# IR_Sensor.net
KiCad netlist of a schematic drawn in Altium Designer
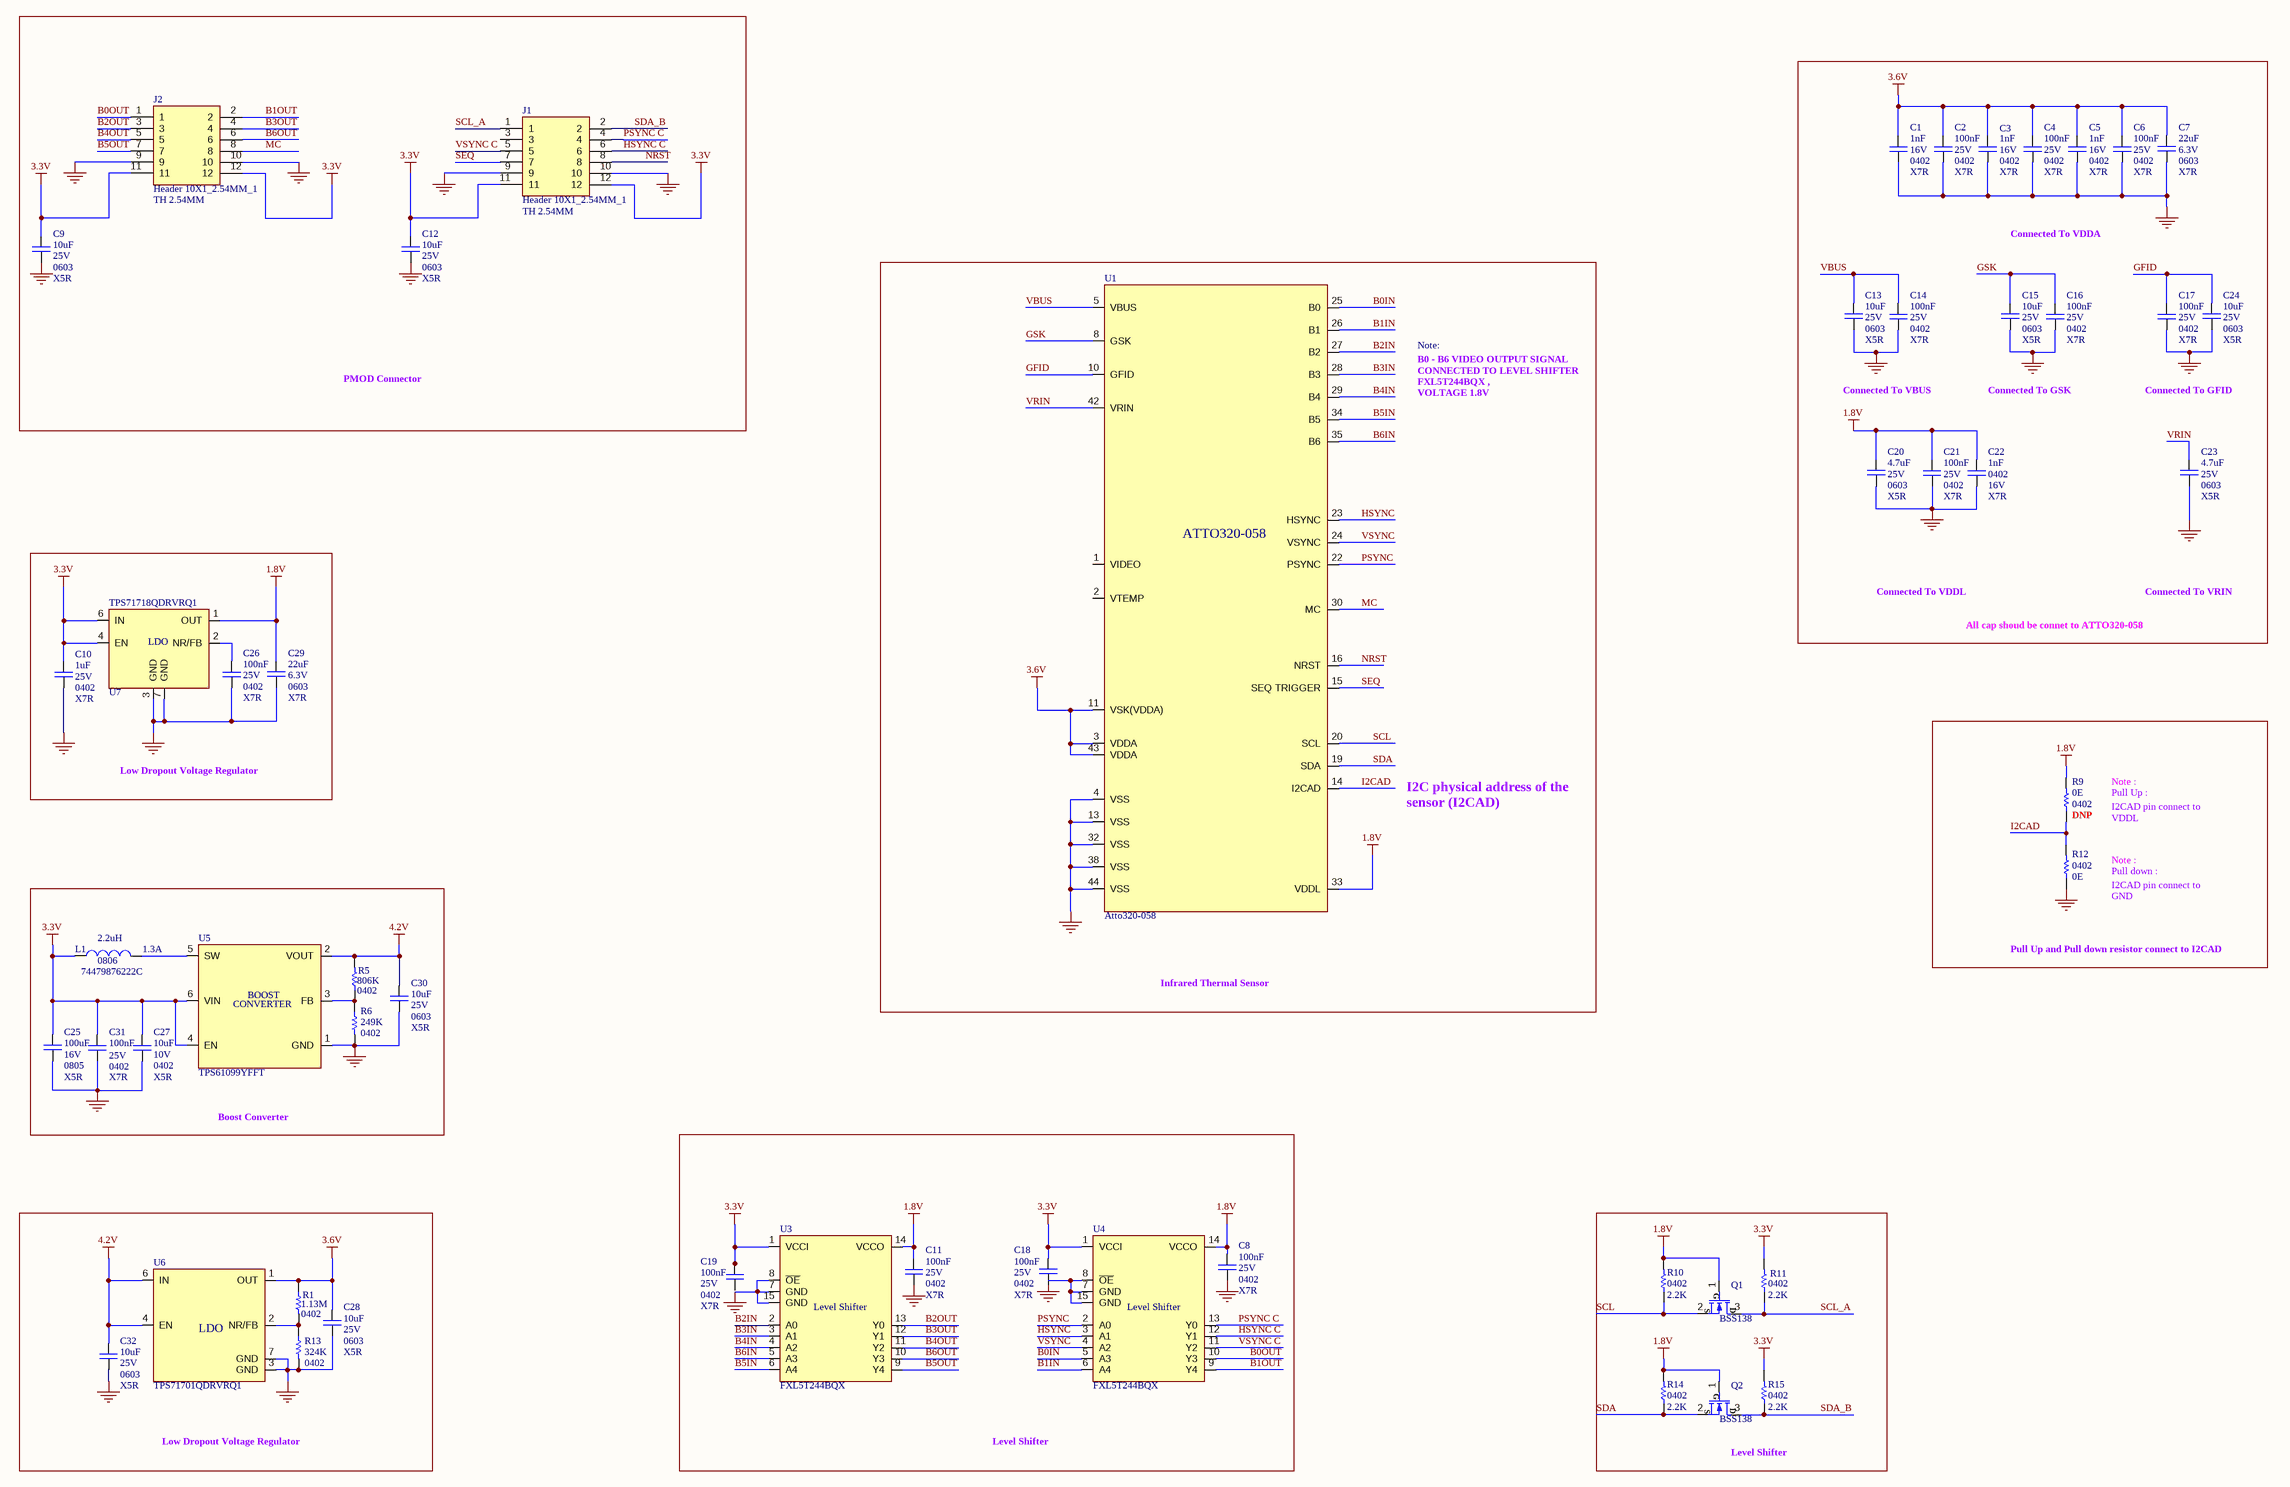
[diagram p0: IR_Sensor.SchDoc]

(export (version "E")
  (design (tool "Eeschema 10.0.6"))
  (components
    (comp (ref "C1")
      (value "1nF")
      (footprint "CAPC0402")
      (description "CAP CER 1nF 16V X7R 0402")
      (fields
        (field (name "VOLTAGE") "16V")
        (field (name "CASE/PACKAGE") "0402")
        (field (name "DIELECTRIC") "X7R")
        (field (name "Comment") "Cap")
      )
      (libsource (lib "CUSTOM TNY290PG") (part "Cap"))
    )
    (comp (ref "C2")
      (value "100nF")
      (footprint "CAPC0402")
      (description "CAP CER 100nF 25V X7R 0402")
      (fields
        (field (name "VOLTAGE") "25V")
        (field (name "CASE/PACKAGE") "0402")
        (field (name "DIELECTRIC") "X7R")
        (field (name "Comment") "Cap")
      )
      (libsource (lib "CUSTOM TNY290PG") (part "Cap"))
    )
    (comp (ref "C3")
      (value "1nF")
      (footprint "CAPC0402")
      (description "CAP CER 1nF 16V X7R 0402")
      (fields
        (field (name "VOLTAGE") "16V")
        (field (name "CASE/PACKAGE") "0402")
        (field (name "DIELECTRIC") "X7R")
        (field (name "Comment") "Cap")
      )
      (libsource (lib "CUSTOM TNY290PG") (part "Cap"))
    )
    (comp (ref "C4")
      (value "100nF")
      (footprint "CAPC0402")
      (description "CAP CER 100nF 25V X7R 0402")
      (fields
        (field (name "VOLTAGE") "25V")
        (field (name "CASE/PACKAGE") "0402")
        (field (name "DIELECTRIC") "X7R")
        (field (name "Comment") "Cap")
      )
      (libsource (lib "CUSTOM TNY290PG") (part "Cap"))
    )
    (comp (ref "C5")
      (value "1nF")
      (footprint "CAPC0402")
      (description "CAP CER 1nF 16V X7R 0402")
      (fields
        (field (name "VOLTAGE") "16V")
        (field (name "CASE/PACKAGE") "0402")
        (field (name "DIELECTRIC") "X7R")
        (field (name "Comment") "Cap")
      )
      (libsource (lib "CUSTOM TNY290PG") (part "Cap"))
    )
    (comp (ref "C6")
      (value "100nF")
      (footprint "CAPC0402")
      (description "CAP CER 100nF 25V X7R 0402")
      (fields
        (field (name "VOLTAGE") "25V")
        (field (name "CASE/PACKAGE") "0402")
        (field (name "DIELECTRIC") "X7R")
        (field (name "Comment") "Cap")
      )
      (libsource (lib "CUSTOM TNY290PG") (part "Cap"))
    )
    (comp (ref "C7")
      (value "22uF")
      (footprint "CAPC0603")
      (description "CAP CER 22uF 6.3V X7R 0603")
      (fields
        (field (name "VOLTAGE") "6.3V")
        (field (name "CASE/PACKAGE") "0603")
        (field (name "DIELECTRIC") "X7R")
        (field (name "Comment") "Cap")
      )
      (libsource (lib "CUSTOM TNY290PG") (part "Cap"))
    )
    (comp (ref "C8")
      (value "100nF")
      (footprint "CAPC0402")
      (description "CAP CER 100nF 25V X7R 0402")
      (fields
        (field (name "VOLTAGE") "25V")
        (field (name "CASE/PACKAGE") "0402")
        (field (name "DIELECTRIC") "X7R")
        (field (name "Comment") "Cap")
      )
      (libsource (lib "CUSTOM TNY290PG") (part "Cap"))
    )
    (comp (ref "C9")
      (value "10uF")
      (footprint "CAPC0603")
      (description "CAP CER 10uF 25V X5R 0603")
      (fields
        (field (name "VOLTAGE") "25V")
        (field (name "CASE/PACKAGE") "0603")
        (field (name "DIELECTRIC") "X5R")
        (field (name "Comment") "Cap")
      )
      (libsource (lib "CUSTOM TNY290PG") (part "Cap"))
    )
    (comp (ref "C10")
      (value "1uF")
      (footprint "CAPC0402")
      (description "CAP CER 1uF 25V X7R 0402")
      (fields
        (field (name "VOLTAGE") "25V")
        (field (name "CASE/PACKAGE") "0402")
        (field (name "DIELECTRIC") "X7R")
        (field (name "Comment") "Cap")
      )
      (libsource (lib "CUSTOM TNY290PG") (part "Cap"))
    )
    (comp (ref "C11")
      (value "100nF")
      (footprint "CAPC0402")
      (description "CAP CER 100nF 25V X7R 0402")
      (fields
        (field (name "VOLTAGE") "25V")
        (field (name "CASE/PACKAGE") "0402")
        (field (name "DIELECTRIC") "X7R")
        (field (name "Comment") "Cap")
      )
      (libsource (lib "CUSTOM TNY290PG") (part "Cap"))
    )
    (comp (ref "C12")
      (value "10uF")
      (footprint "CAPC0603")
      (description "CAP CER 10uF 25V X5R 0603")
      (fields
        (field (name "VOLTAGE") "25V")
        (field (name "CASE/PACKAGE") "0603")
        (field (name "DIELECTRIC") "X5R")
        (field (name "Comment") "Cap")
      )
      (libsource (lib "CUSTOM TNY290PG") (part "Cap"))
    )
    (comp (ref "C13")
      (value "10uF")
      (footprint "CAPC0603")
      (description "CAP CER 10uF 25V X5R 0603")
      (fields
        (field (name "VOLTAGE") "25V")
        (field (name "CASE/PACKAGE") "0603")
        (field (name "DIELECTRIC") "X5R")
        (field (name "Comment") "Cap")
      )
      (libsource (lib "CUSTOM TNY290PG") (part "Cap"))
    )
    (comp (ref "C14")
      (value "100nF")
      (footprint "CAPC0402")
      (description "CAP CER 100nF 25V X7R 0402")
      (fields
        (field (name "VOLTAGE") "25V")
        (field (name "CASE/PACKAGE") "0402")
        (field (name "DIELECTRIC") "X7R")
        (field (name "Comment") "Cap")
      )
      (libsource (lib "CUSTOM TNY290PG") (part "Cap"))
    )
    (comp (ref "C15")
      (value "10uF")
      (footprint "CAPC0603")
      (description "CAP CER 10uF 25V X5R 0603")
      (fields
        (field (name "VOLTAGE") "25V")
        (field (name "CASE/PACKAGE") "0603")
        (field (name "DIELECTRIC") "X5R")
        (field (name "Comment") "Cap")
      )
      (libsource (lib "CUSTOM TNY290PG") (part "Cap"))
    )
    (comp (ref "C16")
      (value "100nF")
      (footprint "CAPC0402")
      (description "CAP CER 100nF 25V X7R 0402")
      (fields
        (field (name "VOLTAGE") "25V")
        (field (name "CASE/PACKAGE") "0402")
        (field (name "DIELECTRIC") "X7R")
        (field (name "Comment") "Cap")
      )
      (libsource (lib "CUSTOM TNY290PG") (part "Cap"))
    )
    (comp (ref "C17")
      (value "100nF")
      (footprint "CAPC0402")
      (description "CAP CER 100nF 25V X7R 0402")
      (fields
        (field (name "VOLTAGE") "25V")
        (field (name "CASE/PACKAGE") "0402")
        (field (name "DIELECTRIC") "X7R")
        (field (name "Comment") "Cap")
      )
      (libsource (lib "CUSTOM TNY290PG") (part "Cap"))
    )
    (comp (ref "C18")
      (value "100nF")
      (footprint "CAPC0402")
      (description "CAP CER 100nF 25V X7R 0402")
      (fields
        (field (name "VOLTAGE") "25V")
        (field (name "CASE/PACKAGE") "0402")
        (field (name "DIELECTRIC") "X7R")
        (field (name "Comment") "Cap")
      )
      (libsource (lib "CUSTOM TNY290PG") (part "Cap"))
    )
    (comp (ref "C19")
      (value "100nF")
      (footprint "CAPC0402")
      (description "CAP CER 100nF 25V X7R 0402")
      (fields
        (field (name "VOLTAGE") "25V")
        (field (name "CASE/PACKAGE") "0402")
        (field (name "DIELECTRIC") "X7R")
        (field (name "Comment") "Cap")
      )
      (libsource (lib "CUSTOM TNY290PG") (part "Cap"))
    )
    (comp (ref "C20")
      (value "4.7uF")
      (footprint "CAPC0603")
      (description "CAP CER 4.7uF 25V X5R 0603")
      (fields
        (field (name "CASE/PACKAGE") "0603")
        (field (name "DIELECTRIC") "X5R")
        (field (name "VOLTAGE") "25V")
        (field (name "Comment") "Cap")
      )
      (libsource (lib "CUSTOM TNY290PG") (part "Cap"))
    )
    (comp (ref "C21")
      (value "100nF")
      (footprint "CAPC0402")
      (description "CAP CER 100nF 25V X7R 0402")
      (fields
        (field (name "VOLTAGE") "25V")
        (field (name "CASE/PACKAGE") "0402")
        (field (name "DIELECTRIC") "X7R")
        (field (name "Comment") "Cap")
      )
      (libsource (lib "CUSTOM TNY290PG") (part "Cap"))
    )
    (comp (ref "C22")
      (value "1nF")
      (footprint "CAPC0402")
      (description "CAP CER 1nF 16V X7R 0402")
      (fields
        (field (name "VOLTAGE") "16V")
        (field (name "CASE/PACKAGE") "0402")
        (field (name "DIELECTRIC") "X7R")
        (field (name "Comment") "Cap")
      )
      (libsource (lib "CUSTOM TNY290PG") (part "Cap"))
    )
    (comp (ref "C23")
      (value "4.7uF")
      (footprint "CAPC0603")
      (description "CAP CER 4.7uF 25V X5R 0603")
      (fields
        (field (name "VOLTAGE") "25V")
        (field (name "CASE/PACKAGE") "0603")
        (field (name "DIELECTRIC") "X5R")
        (field (name "Comment") "Cap")
      )
      (libsource (lib "CUSTOM TNY290PG") (part "Cap"))
    )
    (comp (ref "C24")
      (value "10uF")
      (footprint "CAPC0603")
      (description "CAP CER 10uF 25V X5R 0603")
      (fields
        (field (name "VOLTAGE") "25V")
        (field (name "CASE/PACKAGE") "0603")
        (field (name "DIELECTRIC") "X5R")
        (field (name "Comment") "Cap")
      )
      (libsource (lib "CUSTOM TNY290PG") (part "Cap"))
    )
    (comp (ref "C25")
      (value "100uF")
      (footprint "CAPC0805")
      (description "CAP CER 100uF 16V X5R 0805")
      (fields
        (field (name "CASE/PACKAGE") "0805")
        (field (name "DIELECTRIC") "X5R")
        (field (name "VOLTAGE") "16V")
        (field (name "Comment") "Cap")
      )
      (libsource (lib "CUSTOM TNY290PG") (part "Cap"))
    )
    (comp (ref "C26")
      (value "100nF")
      (footprint "CAPC0402")
      (description "CAP CER 100nF 25V X7R 0402")
      (fields
        (field (name "VOLTAGE") "25V")
        (field (name "CASE/PACKAGE") "0402")
        (field (name "DIELECTRIC") "X7R")
        (field (name "Comment") "Cap")
      )
      (libsource (lib "CUSTOM TNY290PG") (part "Cap"))
    )
    (comp (ref "C27")
      (value "10uF")
      (footprint "CAPC0402")
      (description "CAP CER 10uF 0402 10V X5R")
      (fields
        (field (name "VOLTAGE") "10V")
        (field (name "CASE/PACKAGE") "0402")
        (field (name "DIELECTRIC") "X5R")
        (field (name "Comment") "Cap")
      )
      (libsource (lib "CUSTOM TNY290PG") (part "Cap"))
    )
    (comp (ref "C28")
      (value "10uF")
      (footprint "CAPC0603")
      (description "CAP CER 10uF 25V X5R 0603")
      (fields
        (field (name "VOLTAGE") "25V")
        (field (name "CASE/PACKAGE") "0603")
        (field (name "DIELECTRIC") "X5R")
        (field (name "Comment") "Cap")
      )
      (libsource (lib "CUSTOM TNY290PG") (part "Cap"))
    )
    (comp (ref "C29")
      (value "22uF")
      (footprint "CAPC0603")
      (description "CAP CER 22uF 6.3V X7R 0603")
      (fields
        (field (name "VOLTAGE") "6.3V")
        (field (name "CASE/PACKAGE") "0603")
        (field (name "DIELECTRIC") "X7R")
        (field (name "Comment") "Cap")
      )
      (libsource (lib "CUSTOM TNY290PG") (part "Cap"))
    )
    (comp (ref "C30")
      (value "10uF")
      (footprint "CAPC0603")
      (description "CAP CER 10uF 25V X5R 0603")
      (fields
        (field (name "VOLTAGE") "25V")
        (field (name "CASE/PACKAGE") "0603")
        (field (name "DIELECTRIC") "X5R")
        (field (name "Comment") "Cap")
      )
      (libsource (lib "CUSTOM TNY290PG") (part "Cap"))
    )
    (comp (ref "C31")
      (value "100nF")
      (footprint "CAPC0402")
      (description "CAP CER 100nF 25V X7R 0402")
      (fields
        (field (name "VOLTAGE") "25V")
        (field (name "CASE/PACKAGE") "0402")
        (field (name "DIELECTRIC") "X7R")
        (field (name "Comment") "Cap")
      )
      (libsource (lib "CUSTOM TNY290PG") (part "Cap"))
    )
    (comp (ref "C32")
      (value "10uF")
      (footprint "CAPC0603")
      (description "CAP CER 10uF 25V X5R 0603")
      (fields
        (field (name "VOLTAGE") "25V")
        (field (name "CASE/PACKAGE") "0603")
        (field (name "DIELECTRIC") "X5R")
        (field (name "Comment") "Cap")
      )
      (libsource (lib "CUSTOM TNY290PG") (part "Cap"))
    )
    (comp (ref "J1")
      (value "Header 10X1_2.54MM_1")
      (footprint "SAMTEC_HTSW-106-08-L-D-RA")
      (fields (field (name "MANUFACTURER PART NUMBER") "TH 2.54MM"))
      (libsource (lib "CUSTOM SCH") (part "Header 10X1_2.54MM_1"))
    )
    (comp (ref "J2")
      (value "Header 10X1_2.54MM_1")
      (footprint "SAMTEC_HTSW-106-08-L-D-RA")
      (fields (field (name "MANUFACTURER PART NUMBER") "TH 2.54MM"))
      (libsource (lib "CUSTOM SCH") (part "Header 10X1_2.54MM_1"))
    )
    (comp (ref "L1")
      (value "2.2uH")
      (footprint "IND_0402")
      (description "2.2uH 1.3A 210mOhms")
      (fields
        (field (name "CURRENT") "1.3A")
        (field (name "CASE/PACKAGE") "0806")
        (field (name "MANUFACTURER PART NUMBER") "74479876222C")
        (field (name "Comment") "Inductor")
      )
      (libsource (lib "CUSTOM SCH") (part "Inductor"))
    )
    (comp (ref "Q1")
      (value "MOSFET-N Si2302CDS")
      (footprint "BSS138")
      (description "N-Channel 50 V 220mA (Ta) 350mW (Ta) Surface Mount SOT-23")
      (fields (field (name "MANUFACTURER PART NUMBER") "BSS138"))
      (libsource (lib "CUSTOM SCH") (part "bss138_1"))
    )
    (comp (ref "Q2")
      (value "MOSFET-N Si2302CDS")
      (footprint "BSS138")
      (description "N-Channel 50 V 220mA (Ta) 350mW (Ta) Surface Mount SOT-23")
      (fields (field (name "MANUFACTURER PART NUMBER") "BSS138"))
      (libsource (lib "CUSTOM SCH") (part "bss138_1"))
    )
    (comp (ref "R1")
      (value "1.13M")
      (footprint "RESC0402")
      (description "Thick Film Resistor -  1.13M, 1%, 0402")
      (fields (field (name "CASE/PACKAGE") "0402") (field (name "Comment") "Resistor"))
      (libsource (lib "Pd's Sch Lib") (part "Resistor"))
    )
    (comp (ref "R5")
      (value "806K")
      (footprint "RESC0402")
      (description "Thick Film Resistor -  806K, 1%, 0402")
      (fields (field (name "CASE/PACKAGE") "0402") (field (name "Comment") "Resistor"))
      (libsource (lib "Pd's Sch Lib") (part "Resistor"))
    )
    (comp (ref "R6")
      (value "249K")
      (footprint "RESC0402")
      (description "Thick Film Resistor -  249K, 1%, 0402")
      (fields (field (name "CASE/PACKAGE") "0402") (field (name "Comment") "Resistor"))
      (libsource (lib "Pd's Sch Lib") (part "Resistor"))
    )
    (comp (ref "R9")
      (value "0E")
      (footprint "RESC0402")
      (description "Thick Film Resistor -  0E, 1%, 0402")
      (fields (field (name "CASE/PACKAGE") "0402") (field (name "Comment") "Resistor"))
      (libsource (lib "Pd's Sch Lib") (part "Resistor"))
    )
    (comp (ref "R10")
      (value "2.2K")
      (footprint "RESC0402")
      (description "Thick Film Resistor -  2.2k, 1%, 0402")
      (fields (field (name "CASE/PACKAGE") "0402") (field (name "Comment") "Resistor"))
      (libsource (lib "Pd's Sch Lib") (part "Resistor"))
    )
    (comp (ref "R11")
      (value "2.2K")
      (footprint "RESC0402")
      (description "Thick Film Resistor -  2.2k, 1%, 0402")
      (fields (field (name "CASE/PACKAGE") "0402") (field (name "Comment") "Resistor"))
      (libsource (lib "Pd's Sch Lib") (part "Resistor"))
    )
    (comp (ref "R12")
      (value "0E")
      (footprint "RESC0402")
      (description "Thick Film Resistor -  0E, 1%, 0402")
      (fields (field (name "CASE/PACKAGE") "0402") (field (name "Comment") "Resistor"))
      (libsource (lib "Pd's Sch Lib") (part "Resistor"))
    )
    (comp (ref "R13")
      (value "324K")
      (footprint "RESC0402")
      (description "Thick Film Resistor -  324K, 1%, 0402")
      (fields (field (name "CASE/PACKAGE") "0402") (field (name "Comment") "Resistor"))
      (libsource (lib "Pd's Sch Lib") (part "Resistor"))
    )
    (comp (ref "R14")
      (value "2.2K")
      (footprint "RESC0402")
      (description "Thick Film Resistor -  2.2k, 1%, 0402")
      (fields (field (name "CASE/PACKAGE") "0402") (field (name "Comment") "Resistor"))
      (libsource (lib "Pd's Sch Lib") (part "Resistor"))
    )
    (comp (ref "R15")
      (value "2.2K")
      (footprint "RESC0402")
      (description "Thick Film Resistor -  2.2k, 1%, 0402")
      (fields (field (name "CASE/PACKAGE") "0402") (field (name "Comment") "Resistor"))
      (libsource (lib "Pd's Sch Lib") (part "Resistor"))
    )
    (comp (ref "U1")
      (value "Atto320-058")
      (footprint "CQFP130P1823X1823X336-44N")
      (description "tharmal image sensor Atto320-058")
      (fields (field (name "MANUFACTURER PART NUMBER") "ATTO320-058"))
      (libsource (lib "CUSTOM SCH") (part "Atto320-058"))
    )
    (comp (ref "U3")
      (value "FXL5T244BQX")
      (footprint "SamacSys:FXL5T244BQX")
      (description "Voltage Level Translator Unidirectional 1 Circuit 5 Channel 14-DQFN (3x2.5)")
      (libsource (lib "CUSTOM SCH") (part "FXL5T244BQX"))
    )
    (comp (ref "U4")
      (value "FXL5T244BQX")
      (footprint "SamacSys:FXL5T244BQX")
      (description "Voltage Level Translator Unidirectional 1 Circuit 5 Channel 14-DQFN (3x2.5)")
      (libsource (lib "CUSTOM SCH") (part "FXL5T244BQX"))
    )
    (comp (ref "U5")
      (value "TPS61099YFFT")
      (footprint "BGA TPS61099YFFT")
      (description "Boost Switching Regulator IC Positive Adjustable 1.8V 1 Output 800mA (Switch) 6-UFBGA, DSBGA")
      (fields (field (name "MANUFACTURER PART NUMBER") "TPS61099YFFT"))
      (libsource (lib "CUSTOM SCH") (part "TPS61099YFFT"))
    )
    (comp (ref "U6")
      (value "TPS71701QDRVRQ1")
      (footprint "SamacSys:SON65P200X200X80-7N")
      (description "Linear Voltage Regulator IC Positive Adjustable 1 Output 150mA 6-WSON (2x2)")
      (fields (field (name "MANUFACTURER PART NUMBER") "TPS71701QDRVRQ1"))
      (libsource (lib "CUSTOM SCH") (part "TPS71701QDRVRQ1"))
    )
    (comp (ref "U7")
      (value "TPS71718QDRVRQ1")
      (footprint "SamacSys:SON65P200X200X80-7N")
      (description "Linear Voltage Regulator IC Positive Fixed 1 Output 150mA 6-WSON (2x2)")
      (libsource (lib "CUSTOM SCH") (part "TPS71718QDRVRQ1"))
    )
  )
  (nets
    (net (code "2") (name "/B0IN") (class "Default")
      (node (ref "U1") (pin "25") (pinfunction "B0_25") (pintype "passive"))
      (node (ref "U4") (pin "5") (pinfunction "A3_5") (pintype "passive"))
    )
    (net (code "3") (name "/B0OUT") (class "Default")
      (node (ref "J2") (pin "1") (pinfunction "1_1") (pintype "passive"))
      (node (ref "U4") (pin "10") (pinfunction "Y3_10") (pintype "passive"))
    )
    (net (code "4") (name "/B1IN") (class "Default")
      (node (ref "U1") (pin "26") (pinfunction "B1_26") (pintype "passive"))
      (node (ref "U4") (pin "6") (pinfunction "A4_6") (pintype "passive"))
    )
    (net (code "5") (name "/B1OUT") (class "Default")
      (node (ref "J2") (pin "2") (pinfunction "2_2") (pintype "passive"))
      (node (ref "U4") (pin "9") (pinfunction "Y4_9") (pintype "passive"))
    )
    (net (code "6") (name "/B2IN") (class "Default")
      (node (ref "U1") (pin "27") (pinfunction "B2_27") (pintype "passive"))
      (node (ref "U3") (pin "2") (pinfunction "A0_2") (pintype "passive"))
    )
    (net (code "7") (name "/B2OUT") (class "Default")
      (node (ref "J2") (pin "3") (pinfunction "3_3") (pintype "passive"))
      (node (ref "U3") (pin "13") (pinfunction "Y0_13") (pintype "passive"))
    )
    (net (code "8") (name "/B3IN") (class "Default")
      (node (ref "U1") (pin "28") (pinfunction "B3_28") (pintype "passive"))
      (node (ref "U3") (pin "3") (pinfunction "A1_3") (pintype "passive"))
    )
    (net (code "9") (name "/B3OUT") (class "Default")
      (node (ref "J2") (pin "4") (pinfunction "4_4") (pintype "passive"))
      (node (ref "U3") (pin "12") (pinfunction "Y1_12") (pintype "passive"))
    )
    (net (code "10") (name "/B4IN") (class "Default")
      (node (ref "U1") (pin "29") (pinfunction "B4_29") (pintype "passive"))
      (node (ref "U3") (pin "4") (pinfunction "A2_4") (pintype "passive"))
    )
    (net (code "11") (name "/B4OUT") (class "Default")
      (node (ref "J2") (pin "5") (pinfunction "5_5") (pintype "passive"))
      (node (ref "U3") (pin "11") (pinfunction "Y2_11") (pintype "passive"))
    )
    (net (code "12") (name "/B5IN") (class "Default")
      (node (ref "U1") (pin "34") (pinfunction "B5_34") (pintype "passive"))
      (node (ref "U3") (pin "6") (pinfunction "A4_6") (pintype "passive"))
    )
    (net (code "13") (name "/B5OUT") (class "Default")
      (node (ref "J2") (pin "7") (pinfunction "7_7") (pintype "passive"))
      (node (ref "U3") (pin "9") (pinfunction "Y4_9") (pintype "passive"))
    )
    (net (code "14") (name "/B6IN") (class "Default")
      (node (ref "U1") (pin "35") (pinfunction "B6_35") (pintype "passive"))
      (node (ref "U3") (pin "5") (pinfunction "A3_5") (pintype "passive"))
    )
    (net (code "15") (name "/B6OUT") (class "Default")
      (node (ref "J2") (pin "6") (pinfunction "6_6") (pintype "passive"))
      (node (ref "U3") (pin "10") (pinfunction "Y3_10") (pintype "passive"))
    )
    (net (code "16") (name "/GFID") (class "Default")
      (node (ref "C17") (pin "1") (pinfunction "1_1") (pintype "passive"))
      (node (ref "C24") (pin "2") (pinfunction "2_2") (pintype "passive"))
      (node (ref "U1") (pin "10") (pinfunction "GFID_10") (pintype "passive"))
    )
    (net (code "17") (name "/GSK") (class "Default")
      (node (ref "C15") (pin "2") (pinfunction "2_2") (pintype "passive"))
      (node (ref "C16") (pin "1") (pinfunction "1_1") (pintype "passive"))
      (node (ref "U1") (pin "8") (pinfunction "GSK_8") (pintype "passive"))
    )
    (net (code "18") (name "/HSYNC") (class "Default")
      (node (ref "U1") (pin "23") (pinfunction "HSYNC_23") (pintype "passive"))
      (node (ref "U4") (pin "3") (pinfunction "A1_3") (pintype "passive"))
    )
    (net (code "19") (name "/HSYNC C") (class "Default")
      (node (ref "J1") (pin "6") (pinfunction "6_6") (pintype "passive"))
      (node (ref "U4") (pin "12") (pinfunction "Y1_12") (pintype "passive"))
    )
    (net (code "20") (name "/I2CAD") (class "Default")
      (node (ref "R12") (pin "2") (pinfunction "2_2") (pintype "passive"))
      (node (ref "R9") (pin "1") (pinfunction "1_1") (pintype "passive"))
      (node (ref "U1") (pin "14") (pinfunction "I2CAD_14") (pintype "passive"))
    )
    (net (code "21") (name "/MC") (class "Default")
      (node (ref "J2") (pin "8") (pinfunction "8_8") (pintype "passive"))
      (node (ref "U1") (pin "30") (pinfunction "MC_30") (pintype "passive"))
    )
    (net (code "22") (name "/NRST") (class "Default")
      (node (ref "J1") (pin "8") (pinfunction "8_8") (pintype "passive"))
      (node (ref "U1") (pin "16") (pinfunction "NRST_16") (pintype "passive"))
    )
    (net (code "23") (name "/PSYNC") (class "Default")
      (node (ref "U1") (pin "22") (pinfunction "PSYNC_22") (pintype "passive"))
      (node (ref "U4") (pin "2") (pinfunction "A0_2") (pintype "passive"))
    )
    (net (code "24") (name "/PSYNC C") (class "Default")
      (node (ref "J1") (pin "4") (pinfunction "4_4") (pintype "passive"))
      (node (ref "U4") (pin "13") (pinfunction "Y0_13") (pintype "passive"))
    )
    (net (code "25") (name "/SCL") (class "Default")
      (node (ref "Q1") (pin "2") (pinfunction "S_2") (pintype "passive"))
      (node (ref "R10") (pin "1") (pinfunction "1_1") (pintype "passive"))
      (node (ref "U1") (pin "20") (pinfunction "SCL_20") (pintype "passive"))
    )
    (net (code "26") (name "/SCL_A") (class "Default")
      (node (ref "J1") (pin "1") (pinfunction "1_1") (pintype "passive"))
      (node (ref "Q1") (pin "3") (pinfunction "D_3") (pintype "passive"))
      (node (ref "R11") (pin "1") (pinfunction "1_1") (pintype "passive"))
    )
    (net (code "27") (name "/SDA") (class "Default")
      (node (ref "Q2") (pin "2") (pinfunction "S_2") (pintype "passive"))
      (node (ref "R14") (pin "1") (pinfunction "1_1") (pintype "passive"))
      (node (ref "U1") (pin "19") (pinfunction "SDA_19") (pintype "passive"))
    )
    (net (code "28") (name "/SDA_B") (class "Default")
      (node (ref "J1") (pin "2") (pinfunction "2_2") (pintype "passive"))
      (node (ref "Q2") (pin "3") (pinfunction "D_3") (pintype "passive"))
      (node (ref "R15") (pin "1") (pinfunction "1_1") (pintype "passive"))
    )
    (net (code "29") (name "/SEQ") (class "Default")
      (node (ref "J1") (pin "7") (pinfunction "7_7") (pintype "passive"))
      (node (ref "U1") (pin "15") (pinfunction "SEQ_TRIGGER_15") (pintype "passive"))
    )
    (net (code "30") (name "/VBUS") (class "Default")
      (node (ref "C13") (pin "2") (pinfunction "2_2") (pintype "passive"))
      (node (ref "C14") (pin "1") (pinfunction "1_1") (pintype "passive"))
      (node (ref "U1") (pin "5") (pinfunction "VBUS_5") (pintype "passive"))
    )
    (net (code "31") (name "/VRIN") (class "Default")
      (node (ref "C23") (pin "2") (pinfunction "2_2") (pintype "passive"))
      (node (ref "U1") (pin "42") (pinfunction "VRIN_42") (pintype "passive"))
    )
    (net (code "32") (name "/VSYNC") (class "Default")
      (node (ref "U1") (pin "24") (pinfunction "VSYNC_24") (pintype "passive"))
      (node (ref "U4") (pin "4") (pinfunction "A2_4") (pintype "passive"))
    )
    (net (code "33") (name "/VSYNC C") (class "Default")
      (node (ref "J1") (pin "5") (pinfunction "5_5") (pintype "passive"))
      (node (ref "U4") (pin "11") (pinfunction "Y2_11") (pintype "passive"))
    )
    (net (code "34") (name "1.8V") (class "Default")
      (node (ref "C11") (pin "1") (pinfunction "1_1") (pintype "passive"))
      (node (ref "C20") (pin "2") (pinfunction "2_2") (pintype "passive"))
      (node (ref "C21") (pin "1") (pinfunction "1_1") (pintype "passive"))
      (node (ref "C22") (pin "1") (pinfunction "1_1") (pintype "passive"))
      (node (ref "C29") (pin "2") (pinfunction "2_2") (pintype "passive"))
      (node (ref "C8") (pin "1") (pinfunction "1_1") (pintype "passive"))
      (node (ref "Q1") (pin "1") (pinfunction "G_1") (pintype "passive"))
      (node (ref "Q2") (pin "1") (pinfunction "G_1") (pintype "passive"))
      (node (ref "R10") (pin "2") (pinfunction "2_2") (pintype "passive"))
      (node (ref "R14") (pin "2") (pinfunction "2_2") (pintype "passive"))
      (node (ref "R9") (pin "2") (pinfunction "2_2") (pintype "passive"))
      (node (ref "U1") (pin "33") (pinfunction "VDDL_33") (pintype "passive"))
      (node (ref "U3") (pin "14") (pinfunction "VCCO_14") (pintype "passive"))
      (node (ref "U4") (pin "14") (pinfunction "VCCO_14") (pintype "passive"))
      (node (ref "U7") (pin "1") (pinfunction "OUT_1") (pintype "passive"))
    )
    (net (code "35") (name "3.3V") (class "Default")
      (node (ref "C10") (pin "1") (pinfunction "1_1") (pintype "passive"))
      (node (ref "C12") (pin "2") (pinfunction "2_2") (pintype "passive"))
      (node (ref "C18") (pin "2") (pinfunction "2_2") (pintype "passive"))
      (node (ref "C19") (pin "2") (pinfunction "2_2") (pintype "passive"))
      (node (ref "C25") (pin "2") (pinfunction "2_2") (pintype "passive"))
      (node (ref "C27") (pin "1") (pinfunction "1_1") (pintype "passive"))
      (node (ref "C31") (pin "1") (pinfunction "1_1") (pintype "passive"))
      (node (ref "C9") (pin "2") (pinfunction "2_2") (pintype "passive"))
      (node (ref "J1") (pin "11") (pinfunction "11_11") (pintype "passive"))
      (node (ref "J1") (pin "12") (pinfunction "12_12") (pintype "passive"))
      (node (ref "J2") (pin "11") (pinfunction "11_11") (pintype "passive"))
      (node (ref "J2") (pin "12") (pinfunction "12_12") (pintype "passive"))
      (node (ref "L1") (pin "1") (pinfunction "1_1") (pintype "passive"))
      (node (ref "R11") (pin "2") (pinfunction "2_2") (pintype "passive"))
      (node (ref "R15") (pin "2") (pinfunction "2_2") (pintype "passive"))
      (node (ref "U3") (pin "1") (pinfunction "VCCI_1") (pintype "passive"))
      (node (ref "U4") (pin "1") (pinfunction "VCCI_1") (pintype "passive"))
      (node (ref "U5") (pin "4") (pinfunction "EN_4") (pintype "passive"))
      (node (ref "U5") (pin "6") (pinfunction "VIN_6") (pintype "passive"))
      (node (ref "U7") (pin "4") (pinfunction "EN_4") (pintype "passive"))
      (node (ref "U7") (pin "6") (pinfunction "IN_6") (pintype "passive"))
    )
    (net (code "36") (name "3.6V") (class "Default")
      (node (ref "C1") (pin "1") (pinfunction "1_1") (pintype "passive"))
      (node (ref "C2") (pin "1") (pinfunction "1_1") (pintype "passive"))
      (node (ref "C28") (pin "2") (pinfunction "2_2") (pintype "passive"))
      (node (ref "C3") (pin "1") (pinfunction "1_1") (pintype "passive"))
      (node (ref "C4") (pin "1") (pinfunction "1_1") (pintype "passive"))
      (node (ref "C5") (pin "1") (pinfunction "1_1") (pintype "passive"))
      (node (ref "C6") (pin "1") (pinfunction "1_1") (pintype "passive"))
      (node (ref "C7") (pin "2") (pinfunction "2_2") (pintype "passive"))
      (node (ref "R1") (pin "1") (pinfunction "1_1") (pintype "passive"))
      (node (ref "U1") (pin "11") (pinfunction "VSK(VDDA)_11") (pintype "passive"))
      (node (ref "U1") (pin "3") (pinfunction "VDDA_3") (pintype "passive"))
      (node (ref "U1") (pin "43") (pinfunction "VDDA_43") (pintype "passive"))
      (node (ref "U6") (pin "1") (pinfunction "OUT_1") (pintype "passive"))
    )
    (net (code "37") (name "4.2V") (class "Default")
      (node (ref "C30") (pin "2") (pinfunction "2_2") (pintype "passive"))
      (node (ref "C32") (pin "2") (pinfunction "2_2") (pintype "passive"))
      (node (ref "R5") (pin "2") (pinfunction "2_2") (pintype "passive"))
      (node (ref "U5") (pin "2") (pinfunction "VOUT_2") (pintype "passive"))
      (node (ref "U6") (pin "4") (pinfunction "EN_4") (pintype "passive"))
      (node (ref "U6") (pin "6") (pinfunction "IN_6") (pintype "passive"))
    )
    (net (code "38") (name "GND") (class "Default")
      (node (ref "C1") (pin "2") (pinfunction "2_2") (pintype "passive"))
      (node (ref "C10") (pin "2") (pinfunction "2_2") (pintype "passive"))
      (node (ref "C11") (pin "2") (pinfunction "2_2") (pintype "passive"))
      (node (ref "C12") (pin "1") (pinfunction "1_1") (pintype "passive"))
      (node (ref "C13") (pin "1") (pinfunction "1_1") (pintype "passive"))
      (node (ref "C14") (pin "2") (pinfunction "2_2") (pintype "passive"))
      (node (ref "C15") (pin "1") (pinfunction "1_1") (pintype "passive"))
      (node (ref "C16") (pin "2") (pinfunction "2_2") (pintype "passive"))
      (node (ref "C17") (pin "2") (pinfunction "2_2") (pintype "passive"))
      (node (ref "C2") (pin "2") (pinfunction "2_2") (pintype "passive"))
      (node (ref "C20") (pin "1") (pinfunction "1_1") (pintype "passive"))
      (node (ref "C21") (pin "2") (pinfunction "2_2") (pintype "passive"))
      (node (ref "C22") (pin "2") (pinfunction "2_2") (pintype "passive"))
      (node (ref "C23") (pin "1") (pinfunction "1_1") (pintype "passive"))
      (node (ref "C24") (pin "1") (pinfunction "1_1") (pintype "passive"))
      (node (ref "C25") (pin "1") (pinfunction "1_1") (pintype "passive"))
      (node (ref "C26") (pin "2") (pinfunction "2_2") (pintype "passive"))
      (node (ref "C27") (pin "2") (pinfunction "2_2") (pintype "passive"))
      (node (ref "C28") (pin "1") (pinfunction "1_1") (pintype "passive"))
      (node (ref "C29") (pin "1") (pinfunction "1_1") (pintype "passive"))
      (node (ref "C3") (pin "2") (pinfunction "2_2") (pintype "passive"))
      (node (ref "C30") (pin "1") (pinfunction "1_1") (pintype "passive"))
      (node (ref "C31") (pin "2") (pinfunction "2_2") (pintype "passive"))
      (node (ref "C32") (pin "1") (pinfunction "1_1") (pintype "passive"))
      (node (ref "C4") (pin "2") (pinfunction "2_2") (pintype "passive"))
      (node (ref "C5") (pin "2") (pinfunction "2_2") (pintype "passive"))
      (node (ref "C6") (pin "2") (pinfunction "2_2") (pintype "passive"))
      (node (ref "C7") (pin "1") (pinfunction "1_1") (pintype "passive"))
      (node (ref "C8") (pin "2") (pinfunction "2_2") (pintype "passive"))
      (node (ref "C9") (pin "1") (pinfunction "1_1") (pintype "passive"))
      (node (ref "J1") (pin "10") (pinfunction "10_10") (pintype "passive"))
      (node (ref "J1") (pin "9") (pinfunction "9_9") (pintype "passive"))
      (node (ref "J2") (pin "10") (pinfunction "10_10") (pintype "passive"))
      (node (ref "J2") (pin "9") (pinfunction "9_9") (pintype "passive"))
      (node (ref "R12") (pin "1") (pinfunction "1_1") (pintype "passive"))
      (node (ref "R13") (pin "2") (pinfunction "2_2") (pintype "passive"))
      (node (ref "R6") (pin "2") (pinfunction "2_2") (pintype "passive"))
      (node (ref "U1") (pin "13") (pinfunction "VSS_13") (pintype "passive"))
      (node (ref "U1") (pin "32") (pinfunction "VSS_32") (pintype "passive"))
      (node (ref "U1") (pin "38") (pinfunction "VSS_38") (pintype "passive"))
      (node (ref "U1") (pin "4") (pinfunction "VSS_4") (pintype "passive"))
      (node (ref "U1") (pin "44") (pinfunction "VSS_44") (pintype "passive"))
      (node (ref "U3") (pin "15") (pinfunction "GND_15") (pintype "passive"))
      (node (ref "U3") (pin "7") (pinfunction "GND_7") (pintype "passive"))
      (node (ref "U3") (pin "8") (pinfunction "~{OE}_8") (pintype "passive"))
      (node (ref "U4") (pin "15") (pinfunction "GND_15") (pintype "passive"))
      (node (ref "U4") (pin "7") (pinfunction "GND_7") (pintype "passive"))
      (node (ref "U4") (pin "8") (pinfunction "~{OE}_8") (pintype "passive"))
      (node (ref "U5") (pin "1") (pinfunction "GND_1") (pintype "passive"))
      (node (ref "U6") (pin "3") (pinfunction "GND_3") (pintype "passive"))
      (node (ref "U6") (pin "7") (pinfunction "GND_7") (pintype "passive"))
      (node (ref "U7") (pin "3") (pinfunction "GND_3") (pintype "passive"))
      (node (ref "U7") (pin "7") (pinfunction "GND_7") (pintype "passive"))
    )
    (net (code "39") (name "Net-(U5-FB)") (class "Default")
      (node (ref "R5") (pin "1") (pinfunction "1_1") (pintype "passive"))
      (node (ref "R6") (pin "1") (pinfunction "1_1") (pintype "passive"))
      (node (ref "U5") (pin "3") (pinfunction "FB_3") (pintype "passive"))
    )
    (net (code "40") (name "Net-(U5-SW)") (class "Default")
      (node (ref "L1") (pin "2") (pinfunction "2_2") (pintype "passive"))
      (node (ref "U5") (pin "5") (pinfunction "SW_5") (pintype "passive"))
    )
    (net (code "41") (name "Net-(U6-NR{slash}FB)") (class "Default")
      (node (ref "R1") (pin "2") (pinfunction "2_2") (pintype "passive"))
      (node (ref "R13") (pin "1") (pinfunction "1_1") (pintype "passive"))
      (node (ref "U6") (pin "2") (pinfunction "NR/FB_2") (pintype "passive"))
    )
    (net (code "42") (name "Net-(U7-NR{slash}FB)") (class "Default")
      (node (ref "C26") (pin "1") (pinfunction "1_1") (pintype "passive"))
      (node (ref "U7") (pin "2") (pinfunction "NR/FB_2") (pintype "passive"))
    )
    (net (code "43") (name "unconnected-(C18-Pad1)") (class "Default")
      (node (ref "C18") (pin "1") (pinfunction "1_1") (pintype "passive"))
    )
    (net (code "44") (name "unconnected-(C19-Pad1)") (class "Default")
      (node (ref "C19") (pin "1") (pinfunction "1_1") (pintype "passive"))
    )
    (net (code "45") (name "unconnected-(J1-Pad3)") (class "Default")
      (node (ref "J1") (pin "3") (pinfunction "3_3") (pintype "passive"))
    )
    (net (code "46") (name "unconnected-(U1-VIDEO-Pad1)") (class "Default")
      (node (ref "U1") (pin "1") (pinfunction "VIDEO_1") (pintype "passive"))
    )
    (net (code "47") (name "unconnected-(U1-VTEMP-Pad2)") (class "Default")
      (node (ref "U1") (pin "2") (pinfunction "VTEMP_2") (pintype "passive"))
    )
  )
)
